# 5V_Converter.net
KiCad netlist of a schematic drawn in Altium Designer
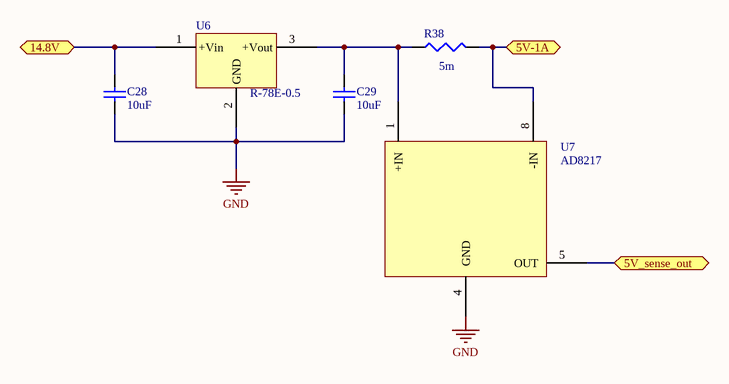
[diagram p0: 5V_Converter.SchDoc]

(export (version "E")
  (design (tool "Eeschema 10.0.6"))
  (components
    (comp (ref "C28")
      (value "10uF")
      (footprint "C1206")
      (description "Capacitor (Semiconductor SIM Model)")
      (fields (field (name "PUBLISHER") "Altium Limited"))
      (libsource (lib "Miscellaneous Devices") (part "Cap Semi"))
    )
    (comp (ref "C29")
      (value "10uF")
      (footprint "C1206")
      (description "Capacitor (Semiconductor SIM Model)")
      (fields (field (name "PUBLISHER") "Altium Limited"))
      (libsource (lib "Miscellaneous Devices") (part "Cap Semi"))
    )
    (comp (ref "R38")
      (value "5m")
      (footprint "J1-0603")
      (description "Resistor")
      (fields (field (name "Comment") "Res3") (field (name "PUBLISHER") "Altium Limited"))
      (libsource (lib "Miscellaneous Devices") (part "Res3"))
    )
    (comp (ref "U6")
      (value "R-78E-0.5")
      (footprint "PCBComponent_1")
      (libsource (lib "Recom-78E5.0-1.0") (part "Component_1"))
    )
    (comp (ref "U7")
      (value "AD8217")
      (footprint "TSOP65P490X110-8N")
      (description "Current Shunt Moniter")
      (libsource (lib "AD8217") (part "Component_1"))
    )
  )
  (nets
    (net (code "1") (name "/5V-1A") (class "Default")
      (node (ref "R38") (pin "2") (pinfunction "2_2") (pintype "passive"))
      (node (ref "U7") (pin "8") (pinfunction "-IN_8") (pintype "passive"))
    )
    (net (code "2") (name "/5V_sense_out") (class "Default")
      (node (ref "U7") (pin "5") (pinfunction "OUT_5") (pintype "passive"))
    )
    (net (code "3") (name "/14.8V") (class "Default")
      (node (ref "C28") (pin "2") (pinfunction "2_2") (pintype "passive"))
      (node (ref "U6") (pin "1") (pinfunction "+Vin_1") (pintype "passive"))
    )
    (net (code "4") (name "GND") (class "Default")
      (node (ref "C28") (pin "1") (pinfunction "1_1") (pintype "passive"))
      (node (ref "C29") (pin "1") (pinfunction "1_1") (pintype "passive"))
      (node (ref "U6") (pin "2") (pinfunction "GND_2") (pintype "passive"))
      (node (ref "U7") (pin "4") (pinfunction "GND_4") (pintype "passive"))
    )
    (net (code "5") (name "Net-(U6-+Vout)") (class "Default")
      (node (ref "C29") (pin "2") (pinfunction "2_2") (pintype "passive"))
      (node (ref "R38") (pin "1") (pinfunction "1_1") (pintype "passive"))
      (node (ref "U6") (pin "3") (pinfunction "+Vout_3") (pintype "passive"))
      (node (ref "U7") (pin "1") (pinfunction "+IN_1") (pintype "passive"))
    )
  )
)
